# TTL_USB.net
KiCad netlist of a schematic drawn in Altium Designer
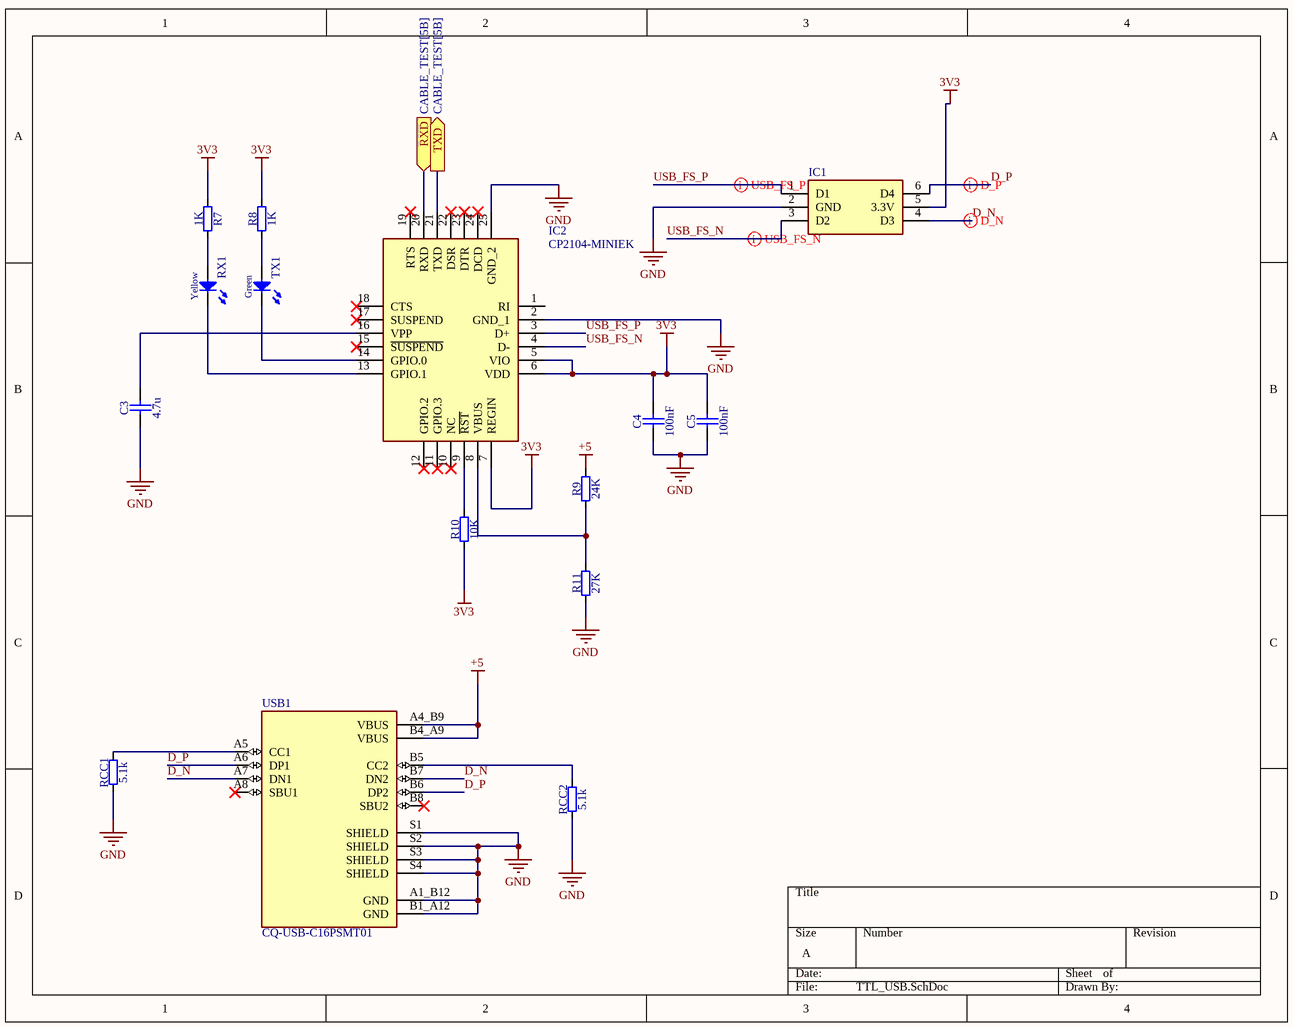
[diagram p0: TTL_USB.SchDoc]

(export (version "E")
  (design (tool "Eeschema 10.0.6"))
  (components
    (comp (ref "C3")
      (value "4.7u")
      (footprint "CAPC2012X135N")
      (description "Non-polarised capacitor")
      (fields
        (field (name "PART NUMBER") "CC0805_100NF_50V_10%_X7R")
        (field (name "VOLTAGE") "50V")
        (field (name "AUTHOR") "CERN DEM JLC")
      )
      (libsource (lib "Capacitors") (part "Capacitor - non polarized"))
    )
    (comp (ref "C4")
      (value "100nF")
      (footprint "CAPC2012X135N")
      (description "Non-polarised capacitor")
      (fields
        (field (name "PART NUMBER") "CC0805_100NF_50V_10%_X7R")
        (field (name "VOLTAGE") "50V")
        (field (name "AUTHOR") "CERN DEM JLC")
      )
      (libsource (lib "Capacitors") (part "Capacitor - non polarized"))
    )
    (comp (ref "C5")
      (value "100nF")
      (footprint "CAPC2012X135N")
      (description "Non-polarised capacitor")
      (fields
        (field (name "PART NUMBER") "CC0805_100NF_50V_10%_X7R")
        (field (name "VOLTAGE") "50V")
        (field (name "AUTHOR") "CERN DEM JLC")
      )
      (libsource (lib "Capacitors") (part "Capacitor - non polarized"))
    )
    (comp (ref "IC1")
      (value "~")
      (footprint "SOT65P210X110-6N")
      (description "Integrated Circuit")
      (fields (field (name "VOLTAGE") "8KV"))
      (libsource (lib "DSC-T.RControlBoard") (part "USBUF02W6"))
    )
    (comp (ref "IC2")
      (value "CP2104-MINIEK")
      (footprint "AMPP:QFN50P400X400X80-25N-D")
      (description "Integrated Circuit")
      (fields (field (name "MOUSER PART NUMBER") "634-CP2104-MINIEK"))
      (libsource (lib "*") (part "CP2104-MINIEK"))
    )
    (comp (ref "R7")
      (value "1K")
      (footprint "RESC2012X60N")
      (description "Resistor - 1%")
      (fields
        (field (name "PART NUMBER") "R0805_24K_1%_0.125W_100PPM")
        (field (name "POWER") "0.125W")
        (field (name "AUTHOR") "CERN DEM JLC")
      )
      (libsource (lib "Resistors") (part "Resistor - 1%"))
    )
    (comp (ref "R8")
      (value "1K")
      (footprint "RESC2012X60N")
      (description "Resistor - 1%")
      (fields
        (field (name "PART NUMBER") "R0805_24K_1%_0.125W_100PPM")
        (field (name "POWER") "0.125W")
        (field (name "AUTHOR") "CERN DEM JLC")
      )
      (libsource (lib "Resistors") (part "Resistor - 1%"))
    )
    (comp (ref "R9")
      (value "24K")
      (footprint "RESC2012X60N")
      (description "Resistor - 1%")
      (fields
        (field (name "PART NUMBER") "R0805_24K_1%_0.125W_100PPM")
        (field (name "POWER") "0.125W")
        (field (name "AUTHOR") "CERN DEM JLC")
      )
      (libsource (lib "Resistors") (part "Resistor - 1%"))
    )
    (comp (ref "R10")
      (value "10K")
      (footprint "RESC2012X60N")
      (description "Resistor - 1%")
      (fields
        (field (name "PART NUMBER") "R0805_24K_1%_0.125W_100PPM")
        (field (name "POWER") "0.125W")
        (field (name "AUTHOR") "CERN DEM JLC")
      )
      (libsource (lib "Resistors") (part "Resistor - 1%"))
    )
    (comp (ref "R11")
      (value "27K")
      (footprint "RESC2012X60N")
      (description "Resistor - 1%")
      (fields
        (field (name "PART NUMBER") "R0805_24K_1%_0.125W_100PPM")
        (field (name "POWER") "0.125W")
        (field (name "AUTHOR") "CERN DEM JLC")
      )
      (libsource (lib "Resistors") (part "Resistor - 1%"))
    )
    (comp (ref "RCC1")
      (value "5.1k")
      (footprint "RESC2012X60N")
      (description "Resistor - 1%")
      (fields
        (field (name "PART NUMBER") "R0805_24K_1%_0.125W_100PPM")
        (field (name "POWER") "0.125W")
        (field (name "AUTHOR") "CERN DEM JLC")
      )
      (libsource (lib "Resistors") (part "Resistor - 1%"))
    )
    (comp (ref "RCC2")
      (value "5.1k")
      (footprint "RESC2012X60N")
      (description "Resistor - 1%")
      (fields
        (field (name "PART NUMBER") "R0805_24K_1%_0.125W_100PPM")
        (field (name "POWER") "0.125W")
        (field (name "AUTHOR") "CERN DEM JLC")
      )
      (libsource (lib "Resistors") (part "Resistor - 1%"))
    )
    (comp (ref "RX1")
      (value "Yellow")
      (footprint "LED_3MM_YELLOW_1C-2A")
      (description "LED Yellow 1C 2A")
      (fields
        (field (name "PART NUMBER") "LED_AVAGO_HLMP-1719")
        (field (name "MANUFACTURER") "AVAGO TECHNOLOGIES")
        (field (name "AUTHOR") "CERN DEM JLC")
      )
      (libsource (lib "ICs And Semiconductors") (part "LED Yellow 1C 2A"))
    )
    (comp (ref "TX1")
      (value "Green")
      (footprint "LED_3MM_GREEN_1C-2A")
      (description "LED Green 1C 2A")
      (fields
        (field (name "PART NUMBER") "LED_AVAGO_HLMP-1790")
        (field (name "MANUFACTURER") "AVAGO TECHNOLOGIES")
        (field (name "AUTHOR") "CERN DEM JLC")
      )
      (libsource (lib "ICs And Semiconductors") (part "LED Green 1C 2A"))
    )
    (comp (ref "USB1")
      (value "CQ-USB-C16PSMT01")
      (footprint "SHENZHEN-CHUANGQIN-TECHNOLOGY_CQ-USB-C16PSMT01")
      (description "C Type USB Type-C Female Plug 16 Pin Connector Power Charger Jack Port")
      (fields (field (name "MF") "Shenzen Chuangqin Technology"))
      (libsource (lib "CQ-USB-C16PSMT01") (part "CQ-USB-C16PSMT01"))
    )
  )
  (nets
    (net (code "1") (name "+5") (class "Default")
      (node (ref "R9") (pin "2") (pinfunction "2_2") (pintype "passive"))
      (node (ref "USB1") (pin "A4_B9") (pinfunction "VBUS_A4_B9") (pintype "power_in"))
      (node (ref "USB1") (pin "B4_A9") (pinfunction "VBUS_B4_A9") (pintype "power_in"))
    )
    (net (code "2") (name "/D_N") (class "Default")
      (node (ref "IC1") (pin "4") (pinfunction "D3_4") (pintype "passive"))
      (node (ref "USB1") (pin "A7") (pinfunction "DN1_A7") (pintype "bidirectional"))
      (node (ref "USB1") (pin "B7") (pinfunction "DN2_B7") (pintype "bidirectional"))
    )
    (net (code "3") (name "/D_P") (class "Default")
      (node (ref "IC1") (pin "6") (pinfunction "D4_6") (pintype "passive"))
      (node (ref "USB1") (pin "A6") (pinfunction "DP1_A6") (pintype "bidirectional"))
      (node (ref "USB1") (pin "B6") (pinfunction "DP2_B6") (pintype "bidirectional"))
    )
    (net (code "4") (name "/RXD") (class "Default")
      (node (ref "IC2") (pin "20") (pinfunction "RXD_20") (pintype "passive"))
    )
    (net (code "5") (name "/TXD") (class "Default")
      (node (ref "IC2") (pin "21") (pinfunction "TXD_21") (pintype "passive"))
    )
    (net (code "6") (name "/USB_FS_N") (class "Default")
      (node (ref "IC1") (pin "3") (pinfunction "D2_3") (pintype "passive"))
      (node (ref "IC2") (pin "4") (pinfunction "D-_4") (pintype "passive"))
    )
    (net (code "7") (name "/USB_FS_P") (class "Default")
      (node (ref "IC1") (pin "1") (pinfunction "D1_1") (pintype "passive"))
      (node (ref "IC2") (pin "3") (pinfunction "D+_3") (pintype "passive"))
    )
    (net (code "8") (name "3V3") (class "Default")
      (node (ref "C4") (pin "2") (pinfunction "2_2") (pintype "passive"))
      (node (ref "C5") (pin "2") (pinfunction "2_2") (pintype "passive"))
      (node (ref "IC1") (pin "5") (pinfunction "3.3V_5") (pintype "passive"))
      (node (ref "IC2") (pin "5") (pinfunction "VIO_5") (pintype "passive"))
      (node (ref "IC2") (pin "6") (pinfunction "VDD_6") (pintype "passive"))
      (node (ref "IC2") (pin "7") (pinfunction "REGIN_7") (pintype "passive"))
      (node (ref "R10") (pin "1") (pinfunction "1_1") (pintype "passive"))
      (node (ref "R7") (pin "1") (pinfunction "1_1") (pintype "passive"))
      (node (ref "R8") (pin "2") (pinfunction "2_2") (pintype "passive"))
    )
    (net (code "9") (name "GND") (class "Default")
      (node (ref "C3") (pin "1") (pinfunction "1_1") (pintype "passive"))
      (node (ref "C4") (pin "1") (pinfunction "1_1") (pintype "passive"))
      (node (ref "C5") (pin "1") (pinfunction "1_1") (pintype "passive"))
      (node (ref "IC1") (pin "2") (pinfunction "GND_2") (pintype "power_in"))
      (node (ref "IC2") (pin "2") (pinfunction "GND_1_2") (pintype "passive"))
      (node (ref "IC2") (pin "25") (pinfunction "GND_2_25") (pintype "passive"))
      (node (ref "R11") (pin "1") (pinfunction "1_1") (pintype "passive"))
      (node (ref "RCC1") (pin "1") (pinfunction "1_1") (pintype "passive"))
      (node (ref "RCC2") (pin "1") (pinfunction "1_1") (pintype "passive"))
      (node (ref "USB1") (pin "A1_B12") (pinfunction "GND_A1_B12") (pintype "power_in"))
      (node (ref "USB1") (pin "B1_A12") (pinfunction "GND_B1_A12") (pintype "power_in"))
      (node (ref "USB1") (pin "S1") (pinfunction "SHIELD_S1") (pintype "passive"))
      (node (ref "USB1") (pin "S2") (pinfunction "SHIELD_S2") (pintype "passive"))
      (node (ref "USB1") (pin "S3") (pinfunction "SHIELD_S3") (pintype "passive"))
      (node (ref "USB1") (pin "S4") (pinfunction "SHIELD_S4") (pintype "passive"))
    )
    (net (code "10") (name "Net-(IC2-GPIO.0)") (class "Default")
      (node (ref "IC2") (pin "14") (pinfunction "GPIO.0_14") (pintype "passive"))
      (node (ref "TX1") (pin "1") (pinfunction "C_1") (pintype "passive"))
    )
    (net (code "11") (name "Net-(IC2-GPIO.1)") (class "Default")
      (node (ref "IC2") (pin "13") (pinfunction "GPIO.1_13") (pintype "passive"))
      (node (ref "RX1") (pin "1") (pinfunction "C_1") (pintype "passive"))
    )
    (net (code "12") (name "Net-(IC2-VBUS)") (class "Default")
      (node (ref "IC2") (pin "8") (pinfunction "VBUS_8") (pintype "passive"))
      (node (ref "R11") (pin "2") (pinfunction "2_2") (pintype "passive"))
      (node (ref "R9") (pin "1") (pinfunction "1_1") (pintype "passive"))
    )
    (net (code "13") (name "Net-(IC2-VPP)") (class "Default")
      (node (ref "C3") (pin "2") (pinfunction "2_2") (pintype "passive"))
      (node (ref "IC2") (pin "16") (pinfunction "VPP_16") (pintype "passive"))
    )
    (net (code "14") (name "Net-(IC2-~{RST})") (class "Default")
      (node (ref "IC2") (pin "9") (pinfunction "~{RST}_9") (pintype "passive"))
      (node (ref "R10") (pin "2") (pinfunction "2_2") (pintype "passive"))
    )
    (net (code "15") (name "Net-(RX1-A)") (class "Default")
      (node (ref "R7") (pin "2") (pinfunction "2_2") (pintype "passive"))
      (node (ref "RX1") (pin "2") (pinfunction "A_2") (pintype "passive"))
    )
    (net (code "16") (name "Net-(TX1-A)") (class "Default")
      (node (ref "R8") (pin "1") (pinfunction "1_1") (pintype "passive"))
      (node (ref "TX1") (pin "2") (pinfunction "A_2") (pintype "passive"))
    )
    (net (code "17") (name "Net-(USB1-CC1)") (class "Default")
      (node (ref "RCC1") (pin "2") (pinfunction "2_2") (pintype "passive"))
      (node (ref "USB1") (pin "A5") (pinfunction "CC1_A5") (pintype "bidirectional"))
    )
    (net (code "18") (name "Net-(USB1-CC2)") (class "Default")
      (node (ref "RCC2") (pin "2") (pinfunction "2_2") (pintype "passive"))
      (node (ref "USB1") (pin "B5") (pinfunction "CC2_B5") (pintype "bidirectional"))
    )
    (net (code "19") (name "unconnected-(IC2-CTS-Pad18)") (class "Default")
      (node (ref "IC2") (pin "18") (pinfunction "CTS_18") (pintype "passive+no_connect"))
    )
    (net (code "20") (name "unconnected-(IC2-DCD-Pad24)") (class "Default")
      (node (ref "IC2") (pin "24") (pinfunction "DCD_24") (pintype "passive+no_connect"))
    )
    (net (code "21") (name "unconnected-(IC2-DSR-Pad22)") (class "Default")
      (node (ref "IC2") (pin "22") (pinfunction "DSR_22") (pintype "passive+no_connect"))
    )
    (net (code "22") (name "unconnected-(IC2-DTR-Pad23)") (class "Default")
      (node (ref "IC2") (pin "23") (pinfunction "DTR_23") (pintype "passive+no_connect"))
    )
    (net (code "23") (name "unconnected-(IC2-GPIO.2-Pad12)") (class "Default")
      (node (ref "IC2") (pin "12") (pinfunction "GPIO.2_12") (pintype "passive+no_connect"))
    )
    (net (code "24") (name "unconnected-(IC2-GPIO.3-Pad11)") (class "Default")
      (node (ref "IC2") (pin "11") (pinfunction "GPIO.3_11") (pintype "passive+no_connect"))
    )
    (net (code "25") (name "unconnected-(IC2-NC-Pad10)") (class "Default")
      (node (ref "IC2") (pin "10") (pinfunction "NC_10") (pintype "passive+no_connect"))
    )
    (net (code "26") (name "unconnected-(IC2-RI-Pad1)") (class "Default")
      (node (ref "IC2") (pin "1") (pinfunction "RI_1") (pintype "passive"))
    )
    (net (code "27") (name "unconnected-(IC2-RTS-Pad19)") (class "Default")
      (node (ref "IC2") (pin "19") (pinfunction "RTS_19") (pintype "passive+no_connect"))
    )
    (net (code "28") (name "unconnected-(IC2-SUSPEND-Pad17)") (class "Default")
      (node (ref "IC2") (pin "17") (pinfunction "SUSPEND_17") (pintype "passive+no_connect"))
    )
    (net (code "29") (name "unconnected-(IC2-~{SUSPEND}-Pad15)") (class "Default")
      (node (ref "IC2") (pin "15") (pinfunction "~{SUSPEND}_15") (pintype "passive+no_connect"))
    )
    (net (code "30") (name "unconnected-(USB1-SBU1-PadA8)") (class "Default")
      (node (ref "USB1") (pin "A8") (pinfunction "SBU1_A8") (pintype "bidirectional+no_connect"))
    )
    (net (code "31") (name "unconnected-(USB1-SBU2-PadB8)") (class "Default")
      (node (ref "USB1") (pin "B8") (pinfunction "SBU2_B8") (pintype "bidirectional+no_connect"))
    )
  )
)
